# Encoder.net
KiCad netlist of a schematic drawn in Altium Designer
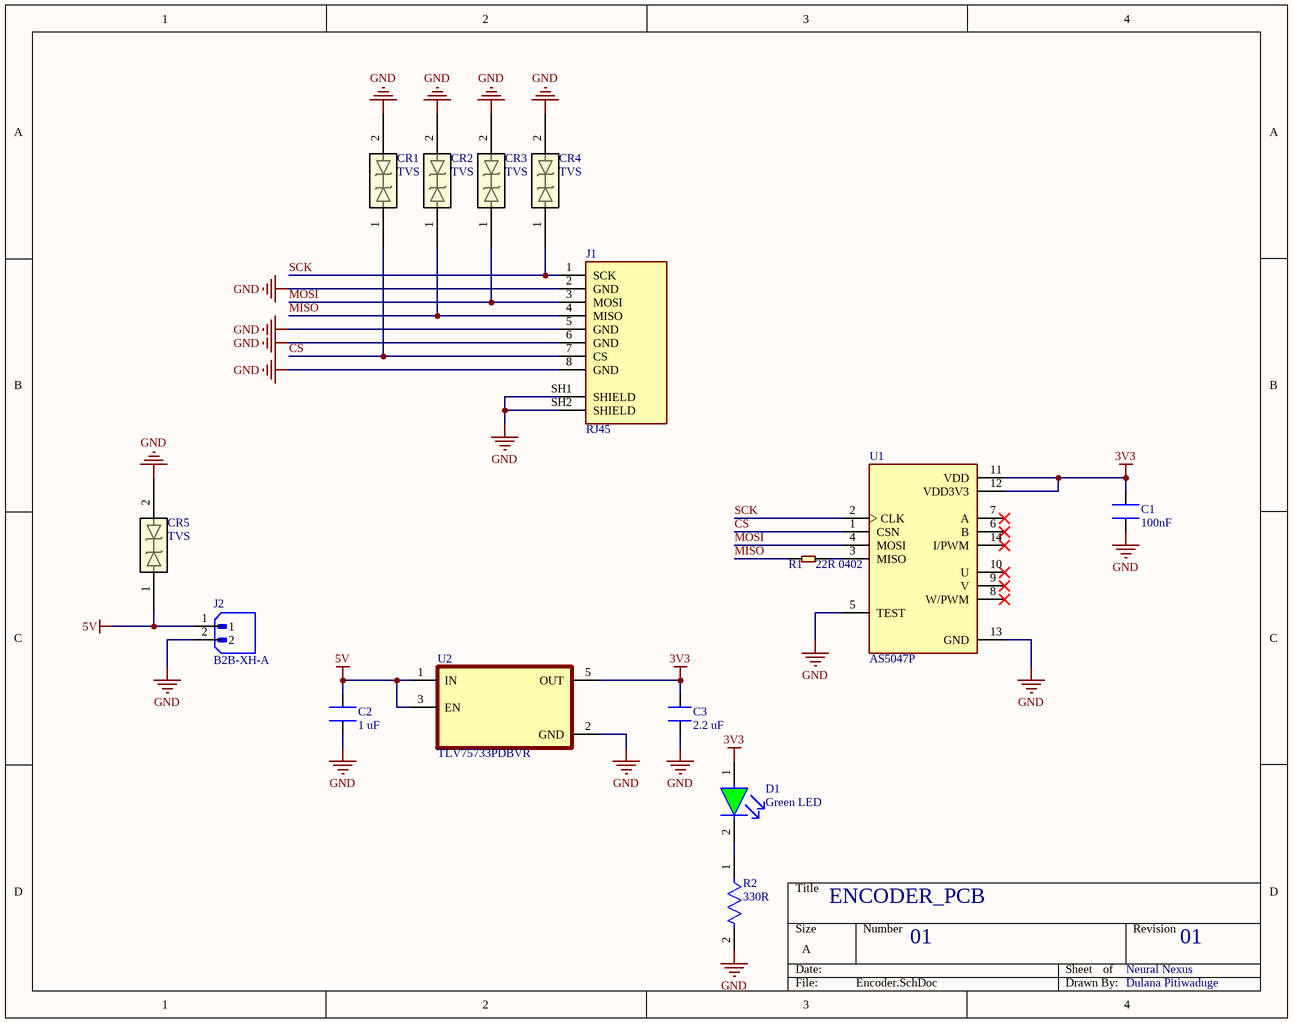
[diagram p0: Encoder.SchDoc]

(export (version "E")
  (design (tool "Eeschema 10.0.6"))
  (components
    (comp (ref "C1")
      (value "100nF")
      (footprint "FP-C0805C-DN-IPC_A")
      (description "Multilayer Ceramic Capacitors MLCC - SMD/SMT 16V 0.1uF X7R 0805 10%")
      (fields
        (field (name "MANUFACTURER") "Yageo Group")
        (field (name "MANUFACTURER PART NUMBER") "C0805C104K4RACTU")
      )
      (libsource (lib "Encoder") (part "C0805C104K4RACTU"))
    )
    (comp (ref "C2")
      (value "1 uF")
      (footprint "CAPC2012X135N")
      (description "1 ÂµF Â±10% 25V Ceramic Capacitor X7R 0805 (2012 Metric)")
      (fields (field (name "MF") "Samsung Electro-Mechanics") (field (name "MP") "CL21B105KAFNNNE"))
      (libsource (lib "Encoder") (part "CL21B105KAFNNNE"))
    )
    (comp (ref "C3")
      (value "2.2 uF")
      (footprint "CAPC2012X135N")
      (description "2.2 ÂµF Â±10% 25V Ceramic Capacitor X7R 0805 (2012 Metric)")
      (fields (field (name "MF") "Samsung") (field (name "MP") "CL21B225KAFNNNE"))
      (libsource (lib "Encoder") (part "CL21B225KAFNNNE"))
    )
    (comp (ref "CR1")
      (value "TVS")
      (footprint "SP0402_LTF")
      (description "TVS DIODE 7VWM 10VC DFN1006-2L")
      (fields
        (field (name "MANUFACTURER_PART_NUMBER") "SP0402B-ULC-01ETG")
        (field (name "COPYRIGHT") "Copyright (C) 2025 Ultra Librarian. All rights reserved.")
      )
      (libsource (lib "Encoder") (part "SP0402B-ULC-01ETG"))
    )
    (comp (ref "CR2")
      (value "TVS")
      (footprint "SP0402_LTF")
      (description "TVS DIODE 7VWM 10VC DFN1006-2L")
      (fields
        (field (name "MANUFACTURER_PART_NUMBER") "SP0402B-ULC-01ETG")
        (field (name "COPYRIGHT") "Copyright (C) 2025 Ultra Librarian. All rights reserved.")
      )
      (libsource (lib "Encoder") (part "SP0402B-ULC-01ETG"))
    )
    (comp (ref "CR3")
      (value "TVS")
      (footprint "SP0402_LTF")
      (description "TVS DIODE 7VWM 10VC DFN1006-2L")
      (fields
        (field (name "MANUFACTURER_PART_NUMBER") "SP0402B-ULC-01ETG")
        (field (name "COPYRIGHT") "Copyright (C) 2025 Ultra Librarian. All rights reserved.")
      )
      (libsource (lib "Encoder") (part "SP0402B-ULC-01ETG"))
    )
    (comp (ref "CR4")
      (value "TVS")
      (footprint "SP0402_LTF")
      (description "TVS DIODE 7VWM 10VC DFN1006-2L")
      (fields
        (field (name "MANUFACTURER_PART_NUMBER") "SP0402B-ULC-01ETG")
        (field (name "COPYRIGHT") "Copyright (C) 2025 Ultra Librarian. All rights reserved.")
      )
      (libsource (lib "Encoder") (part "SP0402B-ULC-01ETG"))
    )
    (comp (ref "CR5")
      (value "TVS")
      (footprint "SP0402_LTF")
      (description "TVS DIODE 7VWM 10VC DFN1006-2L")
      (fields
        (field (name "MANUFACTURER_PART_NUMBER") "SP0402B-ULC-01ETG")
        (field (name "COPYRIGHT") "Copyright (C) 2025 Ultra Librarian. All rights reserved.")
      )
      (libsource (lib "Encoder") (part "SP0402B-ULC-01ETG"))
    )
    (comp (ref "D1")
      (value "Green LED")
      (footprint "FP-SML-LX0805SRC-TR-MFG")
      (description "LED RED CLEAR SMD")
      (fields (field (name "TRONIC PART NO") "LE0011"))
      (libsource (lib "Encoder") (part "RED GREEN"))
    )
    (comp (ref "J1")
      (value "RJ45")
      (footprint "AMPHENOL_RJHSE5380")
      (description "CONN MOD JACK 8P8C R/A SHIELDED")
      (fields (field (name "MF") "Amphenol") (field (name "MP") "RJHSE5380"))
      (libsource (lib "Encoder") (part "RJHSE5380"))
    )
    (comp (ref "J2")
      (value "B2B-XH-A")
      (footprint "JST_B2B-XH-A")
      (fields (field (name "MF") "{'manufacturer': u'JST Sales America Inc.'}"))
      (libsource (lib "Encoder") (part "B2B-XH-A"))
    )
    (comp (ref "R1")
      (value "22R 0402")
      (footprint "R0402")
      (description "22 Ohms Â±1% 0.063W, 1/16W Chip Resistor 0402 (1005 Metric) Moisture Resistant Thick Film")
      (fields (field (name "MF") "Yageo") (field (name "MP") "RC0402FR-0722RL"))
      (libsource (lib "Encoder") (part "SMD-RES-22R-1%-1/16W(0402)"))
    )
    (comp (ref "R2")
      (value "330R")
      (footprint "FP-RMCF0805-IPC_A")
      (description "330Ω ±5% 0.125W 0805 Thick Film Chip Resistor AEC-Q200 compliant")
      (fields (field (name "TOLERANCE") "5%"))
      (libsource (lib "Encoder") (part "CMP-26527-004125-1"))
    )
    (comp (ref "U1")
      (value "AS5047P")
      (footprint "SOP65P640X120-14N")
      (description "Rotary Encoder Magnetic Programmable PWM -")
      (fields (field (name "MF") "ams") (field (name "MP") "AS5047P-ATSM"))
      (libsource (lib "Encoder") (part "AS5047P-ATSM"))
    )
    (comp (ref "U2")
      (value "TLV75733PDBVR")
      (footprint "SOT95P280X145-5N")
      (description "1-A, low-IQ high-accuracy low-dropout (LDO) voltage regulator with enable")
      (fields (field (name "MF") "Texas Instruments"))
      (libsource (lib "Encoder") (part "TLV75733PDBVR"))
    )
  )
  (nets
    (net (code "1") (name "/CS") (class "Default")
      (node (ref "CR1") (pin "1") (pinfunction "1_1") (pintype "passive"))
      (node (ref "J1") (pin "7") (pinfunction "CS_7") (pintype "passive"))
      (node (ref "U1") (pin "1") (pinfunction "CSN_1") (pintype "passive"))
    )
    (net (code "2") (name "/MISO") (class "Default")
      (node (ref "CR2") (pin "1") (pinfunction "1_1") (pintype "passive"))
      (node (ref "J1") (pin "4") (pinfunction "MISO_4") (pintype "passive"))
      (node (ref "R1") (pin "1") (pinfunction "1_1") (pintype "passive"))
    )
    (net (code "3") (name "/MOSI") (class "Default")
      (node (ref "CR3") (pin "1") (pinfunction "1_1") (pintype "passive"))
      (node (ref "J1") (pin "3") (pinfunction "MOSI_3") (pintype "passive"))
      (node (ref "U1") (pin "4") (pinfunction "MOSI_4") (pintype "passive"))
    )
    (net (code "4") (name "/SCK") (class "Default")
      (node (ref "CR4") (pin "1") (pinfunction "1_1") (pintype "passive"))
      (node (ref "J1") (pin "1") (pinfunction "SCK_1") (pintype "passive"))
      (node (ref "U1") (pin "2") (pinfunction "CLK_2") (pintype "passive"))
    )
    (net (code "5") (name "3V3") (class "Default")
      (node (ref "C1") (pin "1") (pinfunction "1_1") (pintype "passive"))
      (node (ref "C3") (pin "2") (pinfunction "2_2") (pintype "passive"))
      (node (ref "D1") (pin "1") (pinfunction "A_1") (pintype "passive"))
      (node (ref "U1") (pin "11") (pinfunction "VDD_11") (pintype "power_in"))
      (node (ref "U1") (pin "12") (pinfunction "VDD3V3_12") (pintype "power_in"))
      (node (ref "U2") (pin "5") (pinfunction "OUT_5") (pintype "passive"))
    )
    (net (code "6") (name "5V") (class "Default")
      (node (ref "C2") (pin "1") (pinfunction "1_1") (pintype "passive"))
      (node (ref "CR5") (pin "1") (pinfunction "1_1") (pintype "passive"))
      (node (ref "J2") (pin "1") (pinfunction "1_1") (pintype "passive"))
      (node (ref "U2") (pin "1") (pinfunction "IN_1") (pintype "passive"))
      (node (ref "U2") (pin "3") (pinfunction "EN_3") (pintype "passive"))
    )
    (net (code "7") (name "GND") (class "Default")
      (node (ref "C1") (pin "2") (pinfunction "2_2") (pintype "passive"))
      (node (ref "C2") (pin "2") (pinfunction "2_2") (pintype "passive"))
      (node (ref "C3") (pin "1") (pinfunction "1_1") (pintype "passive"))
      (node (ref "CR1") (pin "2") (pinfunction "2_2") (pintype "passive"))
      (node (ref "CR2") (pin "2") (pinfunction "2_2") (pintype "passive"))
      (node (ref "CR3") (pin "2") (pinfunction "2_2") (pintype "passive"))
      (node (ref "CR4") (pin "2") (pinfunction "2_2") (pintype "passive"))
      (node (ref "CR5") (pin "2") (pinfunction "2_2") (pintype "passive"))
      (node (ref "J1") (pin "2") (pinfunction "GND_2") (pintype "passive"))
      (node (ref "J1") (pin "5") (pinfunction "GND_5") (pintype "passive"))
      (node (ref "J1") (pin "6") (pinfunction "GND_6") (pintype "passive"))
      (node (ref "J1") (pin "8") (pinfunction "GND_8") (pintype "passive"))
      (node (ref "J1") (pin "SH1") (pinfunction "SHIELD_SH1") (pintype "passive"))
      (node (ref "J1") (pin "SH2") (pinfunction "SHIELD_SH2") (pintype "passive"))
      (node (ref "J2") (pin "2") (pinfunction "2_2") (pintype "passive"))
      (node (ref "R2") (pin "2") (pinfunction "2_2") (pintype "passive"))
      (node (ref "U1") (pin "13") (pinfunction "GND_13") (pintype "power_in"))
      (node (ref "U1") (pin "5") (pinfunction "TEST_5") (pintype "passive"))
      (node (ref "U2") (pin "2") (pinfunction "GND_2") (pintype "power_in"))
    )
    (net (code "8") (name "Net-(D1-C)") (class "Default")
      (node (ref "D1") (pin "2") (pinfunction "C_2") (pintype "passive"))
      (node (ref "R2") (pin "1") (pinfunction "1_1") (pintype "passive"))
    )
    (net (code "9") (name "Net-(U1-MISO)") (class "Default")
      (node (ref "R1") (pin "2") (pinfunction "2_2") (pintype "passive"))
      (node (ref "U1") (pin "3") (pinfunction "MISO_3") (pintype "passive"))
    )
    (net (code "10") (name "unconnected-(U1-A-Pad7)") (class "Default")
      (node (ref "U1") (pin "7") (pinfunction "A_7") (pintype "passive+no_connect"))
    )
    (net (code "11") (name "unconnected-(U1-B-Pad6)") (class "Default")
      (node (ref "U1") (pin "6") (pinfunction "B_6") (pintype "passive+no_connect"))
    )
    (net (code "12") (name "unconnected-(U1-I{slash}PWM-Pad14)") (class "Default")
      (node (ref "U1") (pin "14") (pinfunction "I/PWM_14") (pintype "passive+no_connect"))
    )
    (net (code "13") (name "unconnected-(U1-U-Pad10)") (class "Default")
      (node (ref "U1") (pin "10") (pinfunction "U_10") (pintype "passive+no_connect"))
    )
    (net (code "14") (name "unconnected-(U1-V-Pad9)") (class "Default")
      (node (ref "U1") (pin "9") (pinfunction "V_9") (pintype "passive+no_connect"))
    )
    (net (code "15") (name "unconnected-(U1-W{slash}PWM-Pad8)") (class "Default")
      (node (ref "U1") (pin "8") (pinfunction "W/PWM_8") (pintype "passive+no_connect"))
    )
  )
)
